# BW1092_IMU.net
KiCad netlist of a schematic drawn in Altium Designer
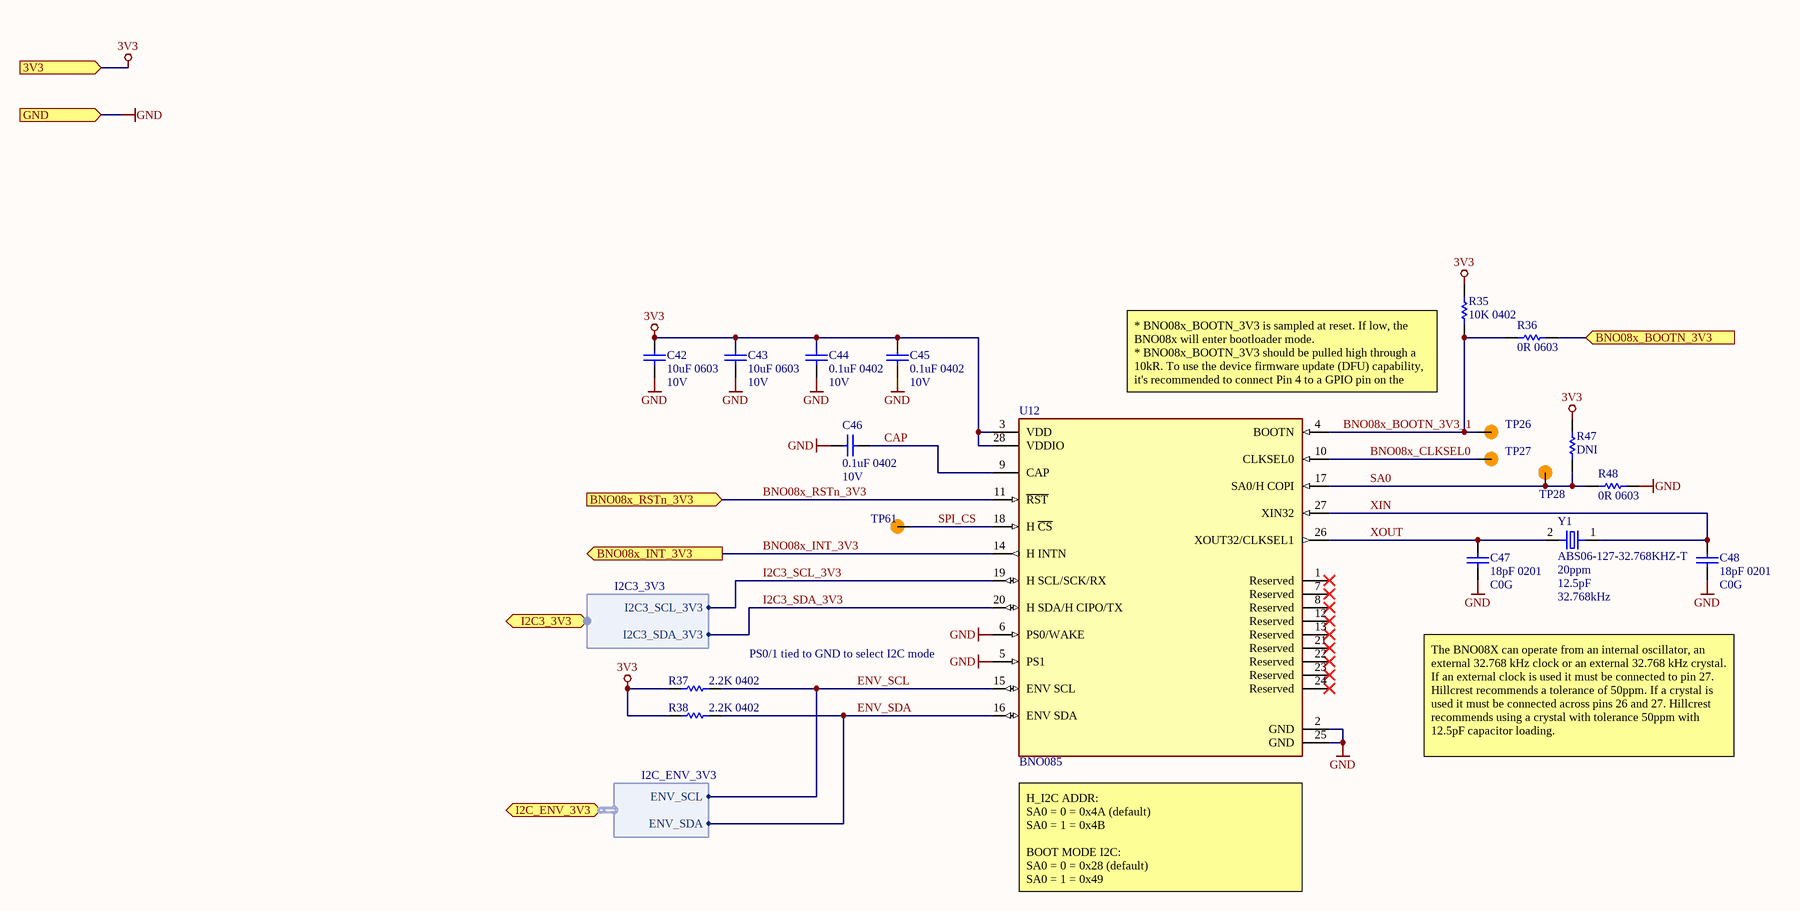
[diagram p0: BW1092_IMU.SchDoc]

(export (version "E")
  (design (tool "Eeschema 10.0.6"))
  (components
    (comp (ref "C42")
      (value "10uF 0603")
      (footprint "CAP_Altium_Vault_Generic:CAPC0603(1608)100_N")
      (description "CAP CER 10UF 10V X5R 0603 20%")
      (fields (field (name "TOLERANCE") "20%") (field (name "VOLTAGE RATING") "10V"))
      (libsource (lib "LuxonisMaster") (part "GRM188R61A106ME69D"))
    )
    (comp (ref "C43")
      (value "10uF 0603")
      (footprint "CAP_Altium_Vault_Generic:CAPC0603(1608)100_N")
      (description "CAP CER 10UF 10V X5R 0603 20%")
      (fields (field (name "TOLERANCE") "20%") (field (name "VOLTAGE RATING") "10V"))
      (libsource (lib "LuxonisMaster") (part "GRM188R61A106ME69D"))
    )
    (comp (ref "C44")
      (value "0.1uF 0402")
      (footprint "CAP_Altium_Vault_Generic:CAPC0402(1005)70_N")
      (description "CAP CER 0.1UF 10V X7R 0402 5%")
      (fields (field (name "TOLERANCE") "5%") (field (name "VOLTAGE RATING") "10V"))
      (libsource (lib "LuxonisMaster") (part "GRM155R71A104JA01D"))
    )
    (comp (ref "C45")
      (value "0.1uF 0402")
      (footprint "CAP_Altium_Vault_Generic:CAPC0402(1005)70_N")
      (description "CAP CER 0.1UF 10V X7R 0402 5%")
      (fields (field (name "TOLERANCE") "5%") (field (name "VOLTAGE RATING") "10V"))
      (libsource (lib "LuxonisMaster") (part "GRM155R71A104JA01D"))
    )
    (comp (ref "C46")
      (value "0.1uF 0402")
      (footprint "CAP_Altium_Vault_Generic:CAPC0402(1005)70_N")
      (description "CAP CER 0.1UF 10V X7R 0402 5%")
      (fields (field (name "TOLERANCE") "5%") (field (name "VOLTAGE RATING") "10V"))
      (libsource (lib "LuxonisMaster") (part "GRM155R71A104JA01D"))
    )
    (comp (ref "C47")
      (value "18pF 0201")
      (footprint "CAP_Altium_Vault_Generic:CAPC0201(0603)33_N")
      (description "Cap Ceramic 18pF 25V C0G 1% Pad SMD 0201 125C T/R")
      (fields (field (name "TOLERANCE") "1%") (field (name "DIELECTRIC") "C0G"))
      (libsource (lib "BW1092_R0M0E0") (part "GRM0335C1E180FA01D"))
    )
    (comp (ref "C48")
      (value "18pF 0201")
      (footprint "CAP_Altium_Vault_Generic:CAPC0201(0603)33_N")
      (description "Cap Ceramic 18pF 25V C0G 1% Pad SMD 0201 125C T/R")
      (fields (field (name "TOLERANCE") "1%") (field (name "DIELECTRIC") "C0G"))
      (libsource (lib "BW1092_R0M0E0") (part "GRM0335C1E180FA01D"))
    )
    (comp (ref "R35")
      (value "10K 0402")
      (footprint "RES_Altium_Vault_Generic:RESC0402(1005)_N")
      (fields (field (name "TOLERANCE") "1%"))
      (libsource (lib "LuxonisMaster") (part "RC0402FR-1310KL"))
    )
    (comp (ref "R36")
      (value "0R 0603")
      (footprint "RES_Altium_Vault_Generic:RESC0603(1608)_N")
      (fields (field (name "TOLERANCE") "5%"))
      (libsource (lib "LuxonisMaster") (part "CRCW06030000Z0EA"))
    )
    (comp (ref "R37")
      (value "2.2K 0402")
      (footprint "RES_Altium_Vault_Generic:RESC0402(1005)_N")
      (description "RES SMD 2.2K OHM 1% 1/16W 0402")
      (fields (field (name "TOLERANCE") "1%"))
      (libsource (lib "LuxonisMaster") (part "RC0402FR-072K2L"))
    )
    (comp (ref "R38")
      (value "2.2K 0402")
      (footprint "RES_Altium_Vault_Generic:RESC0402(1005)_N")
      (description "RES SMD 2.2K OHM 1% 1/16W 0402")
      (fields (field (name "TOLERANCE") "1%"))
      (libsource (lib "LuxonisMaster") (part "RC0402FR-072K2L"))
    )
    (comp (ref "R47")
      (value "DNI")
      (footprint "RES_Altium_Vault_Generic:RESC0603(1608)_N")
      (fields (field (name "TOLERANCE") "5%"))
      (libsource (lib "LuxonisMaster") (part "CRCW06030000Z0EA"))
    )
    (comp (ref "R48")
      (value "0R 0603")
      (footprint "RES_Altium_Vault_Generic:RESC0603(1608)_N")
      (fields (field (name "TOLERANCE") "5%"))
      (libsource (lib "LuxonisMaster") (part "CRCW06030000Z0EA"))
    )
    (comp (ref "TP26")
      (value "TP100_200_NS")
      (footprint "LuxonisMaster:TP100_200_NS")
      (libsource (lib "LuxonisMaster") (part "TEST_POINT"))
    )
    (comp (ref "TP27")
      (value "TP100_200_NS")
      (footprint "LuxonisMaster:TP100_200_NS")
      (libsource (lib "LuxonisMaster") (part "TEST_POINT"))
    )
    (comp (ref "TP28")
      (value "TP100_200_NS")
      (footprint "LuxonisMaster:TP100_200_NS")
      (libsource (lib "LuxonisMaster") (part "TEST_POINT"))
    )
    (comp (ref "TP61")
      (value "TP100_200_NS")
      (footprint "LuxonisMaster:TP100_200_NS")
      (libsource (lib "LuxonisMaster") (part "TEST_POINT"))
    )
    (comp (ref "U12")
      (value "BNO085")
      (footprint "BW1092_R0M0E0:BNO085")
      (description "IMU ACCEL/GYRO/MAG I2C 32BIT")
      (libsource (lib "BW1092_R0M0E0") (part "BNO085"))
    )
    (comp (ref "Y1")
      (value "ABS06-127-32.768KHZ-T")
      (footprint "BW1092_R0M0E0:ABS06-127-32.768KHZ-T")
      (description "CRYSTAL 32.768kHz ±20ppm Crystal 12.5pF 90 kOhms 2-SMD, No Lead")
      (fields
        (field (name "FREQUENCY TOLERANCE") "20ppm")
        (field (name "LOAD CAPACITANCE") "12.5pF")
        (field (name "FREQUENCY") "32.768kHz")
      )
      (libsource (lib "BW1092_R0M0E0") (part "ABS06-127-32.768KHZ-T"))
    )
  )
  (nets
    (net (code "3") (name "/BNO08x_BOOTN_3V3") (class "Default")
      (node (ref "R36") (pin "2") (pinfunction "2_2") (pintype "passive"))
    )
    (net (code "4") (name "/BNO08x_BOOTN_3V3_1") (class "Default")
      (node (ref "R35") (pin "1") (pinfunction "1_1") (pintype "passive"))
      (node (ref "R36") (pin "1") (pinfunction "1_1") (pintype "passive"))
      (node (ref "TP26") (pin "1") (pintype "passive"))
      (node (ref "U12") (pin "4") (pinfunction "BOOTN_4") (pintype "input"))
    )
    (net (code "5") (name "/BNO08x_CLKSEL0") (class "Default")
      (node (ref "TP27") (pin "1") (pintype "passive"))
      (node (ref "U12") (pin "10") (pinfunction "CLKSEL0_10") (pintype "input"))
    )
    (net (code "6") (name "/BNO08x_INT_3V3") (class "Default")
      (node (ref "U12") (pin "14") (pinfunction "H_INTN_14") (pintype "output"))
    )
    (net (code "7") (name "/BNO08x_RSTn_3V3") (class "Default")
      (node (ref "U12") (pin "11") (pinfunction "~{RST}_11") (pintype "input"))
    )
    (net (code "8") (name "/CAP") (class "Default")
      (node (ref "C46") (pin "1") (pinfunction "1_1") (pintype "passive"))
      (node (ref "U12") (pin "9") (pinfunction "CAP_9") (pintype "passive"))
    )
    (net (code "9") (name "/ENV_SCL") (class "Default")
      (node (ref "R37") (pin "2") (pinfunction "2_2") (pintype "passive"))
      (node (ref "U12") (pin "15") (pinfunction "ENV_SCL_15") (pintype "bidirectional"))
    )
    (net (code "10") (name "/ENV_SDA") (class "Default")
      (node (ref "R38") (pin "2") (pinfunction "2_2") (pintype "passive"))
      (node (ref "U12") (pin "16") (pinfunction "ENV_SDA_16") (pintype "bidirectional"))
    )
    (net (code "11") (name "/I2C3_SCL_3V3") (class "Default")
      (node (ref "U12") (pin "19") (pinfunction "H_SCL/SCK/RX_19") (pintype "bidirectional"))
    )
    (net (code "12") (name "/I2C3_SDA_3V3") (class "Default")
      (node (ref "U12") (pin "20") (pinfunction "H_SDA/H_CIPO/TX_20") (pintype "bidirectional"))
    )
    (net (code "13") (name "/SA0") (class "Default")
      (node (ref "R47") (pin "1") (pinfunction "1_1") (pintype "passive"))
      (node (ref "R48") (pin "2") (pinfunction "2_2") (pintype "passive"))
      (node (ref "TP28") (pin "1") (pintype "passive"))
      (node (ref "U12") (pin "17") (pinfunction "SA0/H_COPI_17") (pintype "input"))
    )
    (net (code "14") (name "/SPI_CS") (class "Default")
      (node (ref "TP61") (pin "1") (pintype "passive"))
      (node (ref "U12") (pin "18") (pinfunction "H_~{CS}_18") (pintype "input"))
    )
    (net (code "15") (name "/XIN") (class "Default")
      (node (ref "C48") (pin "2") (pinfunction "2_2") (pintype "passive"))
      (node (ref "U12") (pin "27") (pinfunction "XIN32_27") (pintype "input"))
      (node (ref "Y1") (pin "1") (pinfunction "1_1") (pintype "passive"))
    )
    (net (code "16") (name "/XOUT") (class "Default")
      (node (ref "C47") (pin "2") (pinfunction "2_2") (pintype "passive"))
      (node (ref "U12") (pin "26") (pinfunction "XOUT32/CLKSEL1_26") (pintype "output"))
      (node (ref "Y1") (pin "2") (pinfunction "2_2") (pintype "passive"))
    )
    (net (code "19") (name "3V3") (class "Default")
      (node (ref "C42") (pin "2") (pinfunction "2_2") (pintype "passive"))
      (node (ref "C43") (pin "2") (pinfunction "2_2") (pintype "passive"))
      (node (ref "C44") (pin "2") (pinfunction "2_2") (pintype "passive"))
      (node (ref "C45") (pin "2") (pinfunction "2_2") (pintype "passive"))
      (node (ref "R35") (pin "2") (pinfunction "2_2") (pintype "passive"))
      (node (ref "R37") (pin "1") (pinfunction "1_1") (pintype "passive"))
      (node (ref "R38") (pin "1") (pinfunction "1_1") (pintype "passive"))
      (node (ref "R47") (pin "2") (pinfunction "2_2") (pintype "passive"))
      (node (ref "U12") (pin "28") (pinfunction "VDDIO_28") (pintype "power_in"))
      (node (ref "U12") (pin "3") (pinfunction "VDD_3") (pintype "power_in"))
    )
    (net (code "20") (name "GND") (class "Default")
      (node (ref "C42") (pin "1") (pinfunction "1_1") (pintype "passive"))
      (node (ref "C43") (pin "1") (pinfunction "1_1") (pintype "passive"))
      (node (ref "C44") (pin "1") (pinfunction "1_1") (pintype "passive"))
      (node (ref "C45") (pin "1") (pinfunction "1_1") (pintype "passive"))
      (node (ref "C46") (pin "2") (pinfunction "2_2") (pintype "passive"))
      (node (ref "C47") (pin "1") (pinfunction "1_1") (pintype "passive"))
      (node (ref "C48") (pin "1") (pinfunction "1_1") (pintype "passive"))
      (node (ref "R48") (pin "1") (pinfunction "1_1") (pintype "passive"))
      (node (ref "U12") (pin "2") (pinfunction "GND_2") (pintype "power_in"))
      (node (ref "U12") (pin "25") (pinfunction "GND_25") (pintype "power_in"))
      (node (ref "U12") (pin "5") (pinfunction "PS1_5") (pintype "input"))
      (node (ref "U12") (pin "6") (pinfunction "PS0/WAKE_6") (pintype "input"))
    )
    (net (code "21") (name "unconnected-(U12-Reserved-Pad1)") (class "Default")
      (node (ref "U12") (pin "1") (pinfunction "Reserved_1") (pintype "passive+no_connect"))
    )
    (net (code "22") (name "unconnected-(U12-Reserved-Pad7)") (class "Default")
      (node (ref "U12") (pin "7") (pinfunction "Reserved_7") (pintype "passive+no_connect"))
    )
    (net (code "23") (name "unconnected-(U12-Reserved-Pad8)") (class "Default")
      (node (ref "U12") (pin "8") (pinfunction "Reserved_8") (pintype "passive+no_connect"))
    )
    (net (code "24") (name "unconnected-(U12-Reserved-Pad12)") (class "Default")
      (node (ref "U12") (pin "12") (pinfunction "Reserved_12") (pintype "passive+no_connect"))
    )
    (net (code "25") (name "unconnected-(U12-Reserved-Pad13)") (class "Default")
      (node (ref "U12") (pin "13") (pinfunction "Reserved_13") (pintype "passive+no_connect"))
    )
    (net (code "26") (name "unconnected-(U12-Reserved-Pad21)") (class "Default")
      (node (ref "U12") (pin "21") (pinfunction "Reserved_21") (pintype "passive+no_connect"))
    )
    (net (code "27") (name "unconnected-(U12-Reserved-Pad22)") (class "Default")
      (node (ref "U12") (pin "22") (pinfunction "Reserved_22") (pintype "passive+no_connect"))
    )
    (net (code "28") (name "unconnected-(U12-Reserved-Pad23)") (class "Default")
      (node (ref "U12") (pin "23") (pinfunction "Reserved_23") (pintype "passive+no_connect"))
    )
    (net (code "29") (name "unconnected-(U12-Reserved-Pad24)") (class "Default")
      (node (ref "U12") (pin "24") (pinfunction "Reserved_24") (pintype "passive+no_connect"))
    )
  )
)
